# processor.net
KiCad netlist of a schematic drawn in Altium Designer
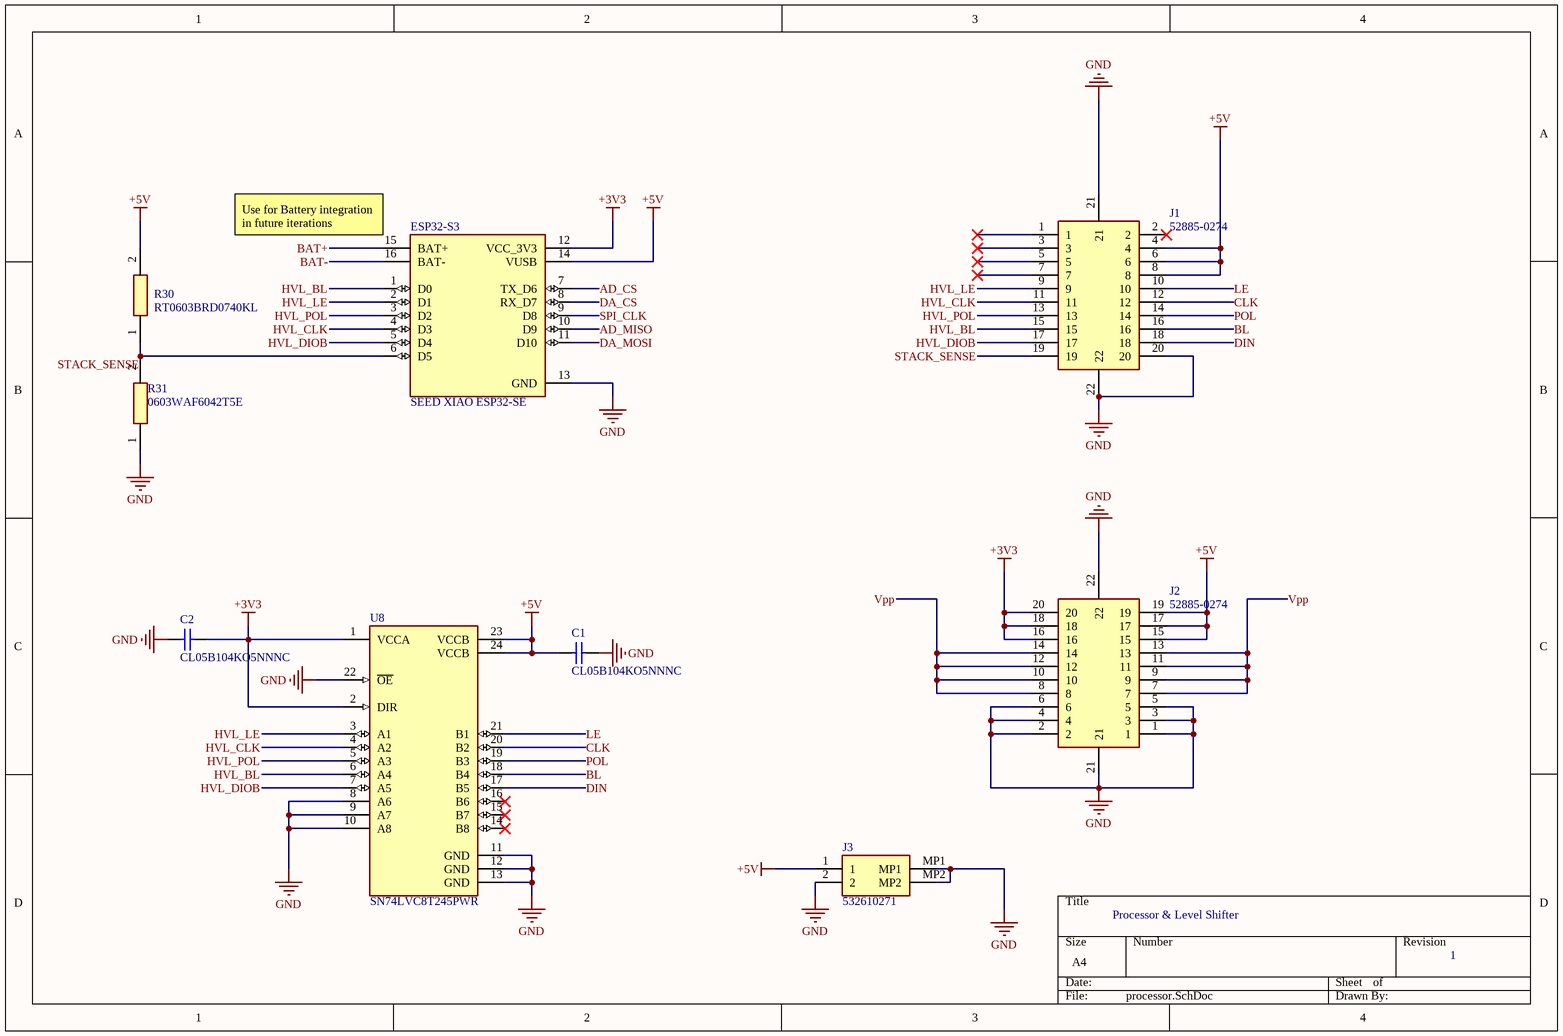
[diagram p0: processor.SchDoc]

(export (version "E")
  (design (tool "Eeschema 10.0.6"))
  (components
    (comp (ref "C1")
      (value "CL05B104KO5NNNC")
      (footprint "CAPC1050X55X23ML05T13")
      (description "Chip Capacitor, 100 nF, +/- 10%, 16 V, -55 to 125 degC, 0402 (1005 Metric), RoHS, Tape and Reel")
      (fields (field (name "MANUFACTURER") "Samsung Electro-Mechanics"))
      (libsource (lib "Altium Content Vault") (part "CAP-NP-2"))
    )
    (comp (ref "C2")
      (value "CL05B104KO5NNNC")
      (footprint "CAPC1050X55X23ML05T13")
      (description "Chip Capacitor, 100 nF, +/- 10%, 16 V, -55 to 125 degC, 0402 (1005 Metric), RoHS, Tape and Reel")
      (fields (field (name "MANUFACTURER") "Samsung Electro-Mechanics"))
      (libsource (lib "Altium Content Vault") (part "CAP-NP-2"))
    )
    (comp (ref "ESP32-S3")
      (value "SEED XIAO ESP32-SE")
      (footprint "PCBComponent_1")
      (libsource (lib "ESP32-S3") (part "Component_1"))
    )
    (comp (ref "J1")
      (value "52885-0274")
      (footprint "528850274")
      (description "Connector")
      (fields (field (name "MOUSER PART NUMBER") "538-52885-0274"))
      (libsource (lib "") (part "52885-0274_1"))
    )
    (comp (ref "J2")
      (value "52885-0274")
      (footprint "528850274")
      (description "Connector")
      (fields (field (name "MOUSER PART NUMBER") "538-52885-0274"))
      (libsource (lib "E_tactile_components") (part "52885-0274"))
    )
    (comp (ref "J3")
      (value "532610271")
      (footprint "SamacSys:532610271")
      (description "C177225")
      (fields
        (field (name "MANUFACTURER_PART_NUMBER") "53261-0271")
        (field (name "MOUSER PART NUMBER") "538-53261-0271")
      )
      (libsource (lib "*") (part "53261-0271"))
    )
    (comp (ref "R30")
      (value "RT0603BRD0740KL")
      (footprint "SamacSys:RESC1608X55N")
      (description "Resistor")
      (fields (field (name "MOUSER PART NUMBER") "603-RT0603BRD0740KL"))
      (libsource (lib "*") (part "RT0603BRD0740KL"))
    )
    (comp (ref "R31")
      (value "0603WAF6042T5E")
      (footprint "SamacSys:RESC1608X55N")
      (description "Resistor")
      (libsource (lib "*") (part "MCT06030C6042FP500"))
    )
    (comp (ref "U8")
      (value "SN74LVC8T245PWR")
      (footprint "FP-PW0024A-MFG")
      (description "IC TRNSLTR BIDIRECTIONAL 24TSSOP")
      (fields
        (field (name "OCTOPART") "https://octopart.com/sn74lvc8t245pwr-texas+instruments-517164")
        (field (name "MANUFACTURER") "Texas Instruments")
      )
      (libsource (lib "Altium Content Vault") (part "51221a7e4c45eff2cf920f7ccaf63e0"))
    )
  )
  (nets
    (net (code "1") (name "+3V3") (class "Default")
      (node (ref "C2") (pin "2") (pinfunction "2_2") (pintype "passive"))
      (node (ref "ESP32-S3") (pin "12") (pinfunction "VCC_3V3_12") (pintype "power_in"))
      (node (ref "J2") (pin "16") (pinfunction "16_16") (pintype "passive"))
      (node (ref "J2") (pin "18") (pinfunction "18_18") (pintype "passive"))
      (node (ref "J2") (pin "20") (pinfunction "20_20") (pintype "passive"))
      (node (ref "U8") (pin "1") (pinfunction "VCCA_1") (pintype "power_in"))
      (node (ref "U8") (pin "2") (pinfunction "DIR_2") (pintype "input"))
    )
    (net (code "2") (name "+5V") (class "Default")
      (node (ref "C1") (pin "1") (pinfunction "1_1") (pintype "passive"))
      (node (ref "ESP32-S3") (pin "14") (pinfunction "VUSB_14") (pintype "power_in"))
      (node (ref "J1") (pin "4") (pinfunction "4_4") (pintype "passive"))
      (node (ref "J1") (pin "6") (pinfunction "6_6") (pintype "passive"))
      (node (ref "J1") (pin "8") (pinfunction "8_8") (pintype "passive"))
      (node (ref "J2") (pin "15") (pinfunction "15_15") (pintype "passive"))
      (node (ref "J2") (pin "17") (pinfunction "17_17") (pintype "passive"))
      (node (ref "J2") (pin "19") (pinfunction "19_19") (pintype "passive"))
      (node (ref "J3") (pin "1") (pinfunction "1_1") (pintype "passive"))
      (node (ref "R30") (pin "2") (pinfunction "2_2") (pintype "passive"))
      (node (ref "U8") (pin "23") (pinfunction "VCCB_23") (pintype "power_in"))
      (node (ref "U8") (pin "24") (pinfunction "VCCB_24") (pintype "power_in"))
    )
    (net (code "3") (name "/AD_CS") (class "Default")
      (node (ref "ESP32-S3") (pin "7") (pinfunction "TX_D6_7") (pintype "bidirectional"))
    )
    (net (code "4") (name "/AD_MISO") (class "Default")
      (node (ref "ESP32-S3") (pin "10") (pinfunction "D9_10") (pintype "bidirectional"))
    )
    (net (code "5") (name "/BAT+") (class "Default")
      (node (ref "ESP32-S3") (pin "15") (pinfunction "BAT+_15") (pintype "passive"))
    )
    (net (code "6") (name "/BAT-") (class "Default")
      (node (ref "ESP32-S3") (pin "16") (pinfunction "BAT-_16") (pintype "passive"))
    )
    (net (code "7") (name "/BL") (class "Default")
      (node (ref "J1") (pin "16") (pinfunction "16_16") (pintype "passive"))
      (node (ref "U8") (pin "18") (pinfunction "B4_18") (pintype "bidirectional"))
    )
    (net (code "8") (name "/CLK") (class "Default")
      (node (ref "J1") (pin "12") (pinfunction "12_12") (pintype "passive"))
      (node (ref "U8") (pin "20") (pinfunction "B2_20") (pintype "bidirectional"))
    )
    (net (code "9") (name "/DA_CS") (class "Default")
      (node (ref "ESP32-S3") (pin "8") (pinfunction "RX_D7_8") (pintype "bidirectional"))
    )
    (net (code "10") (name "/DA_MOSI") (class "Default")
      (node (ref "ESP32-S3") (pin "11") (pinfunction "D10_11") (pintype "bidirectional"))
    )
    (net (code "11") (name "/DIN") (class "Default")
      (node (ref "J1") (pin "18") (pinfunction "18_18") (pintype "passive"))
      (node (ref "U8") (pin "17") (pinfunction "B5_17") (pintype "bidirectional"))
    )
    (net (code "12") (name "/HVL_BL") (class "Default")
      (node (ref "ESP32-S3") (pin "1") (pinfunction "D0_1") (pintype "bidirectional"))
      (node (ref "J1") (pin "15") (pinfunction "15_15") (pintype "passive"))
      (node (ref "U8") (pin "6") (pinfunction "A4_6") (pintype "bidirectional"))
    )
    (net (code "13") (name "/HVL_CLK") (class "Default")
      (node (ref "ESP32-S3") (pin "4") (pinfunction "D3_4") (pintype "bidirectional"))
      (node (ref "J1") (pin "11") (pinfunction "11_11") (pintype "passive"))
      (node (ref "U8") (pin "4") (pinfunction "A2_4") (pintype "bidirectional"))
    )
    (net (code "14") (name "/HVL_DIOB") (class "Default")
      (node (ref "ESP32-S3") (pin "5") (pinfunction "D4_5") (pintype "bidirectional"))
      (node (ref "J1") (pin "17") (pinfunction "17_17") (pintype "passive"))
      (node (ref "U8") (pin "7") (pinfunction "A5_7") (pintype "bidirectional"))
    )
    (net (code "15") (name "/HVL_LE") (class "Default")
      (node (ref "ESP32-S3") (pin "2") (pinfunction "D1_2") (pintype "bidirectional"))
      (node (ref "J1") (pin "9") (pinfunction "9_9") (pintype "passive"))
      (node (ref "U8") (pin "3") (pinfunction "A1_3") (pintype "bidirectional"))
    )
    (net (code "16") (name "/HVL_POL") (class "Default")
      (node (ref "ESP32-S3") (pin "3") (pinfunction "D2_3") (pintype "bidirectional"))
      (node (ref "J1") (pin "13") (pinfunction "13_13") (pintype "passive"))
      (node (ref "U8") (pin "5") (pinfunction "A3_5") (pintype "bidirectional"))
    )
    (net (code "17") (name "/LE") (class "Default")
      (node (ref "J1") (pin "10") (pinfunction "10_10") (pintype "passive"))
      (node (ref "U8") (pin "21") (pinfunction "B1_21") (pintype "bidirectional"))
    )
    (net (code "18") (name "/POL") (class "Default")
      (node (ref "J1") (pin "14") (pinfunction "14_14") (pintype "passive"))
      (node (ref "U8") (pin "19") (pinfunction "B3_19") (pintype "bidirectional"))
    )
    (net (code "19") (name "/SPI_CLK") (class "Default")
      (node (ref "ESP32-S3") (pin "9") (pinfunction "D8_9") (pintype "bidirectional"))
    )
    (net (code "20") (name "/STACK_SENSE") (class "Default")
      (node (ref "ESP32-S3") (pin "6") (pinfunction "D5_6") (pintype "bidirectional"))
      (node (ref "J1") (pin "19") (pinfunction "19_19") (pintype "passive"))
      (node (ref "R30") (pin "1") (pinfunction "1_1") (pintype "passive"))
      (node (ref "R31") (pin "2") (pinfunction "2_2") (pintype "passive"))
    )
    (net (code "21") (name "/Vpp") (class "Default")
      (node (ref "J2") (pin "10") (pinfunction "10_10") (pintype "passive"))
      (node (ref "J2") (pin "11") (pinfunction "11_11") (pintype "passive"))
      (node (ref "J2") (pin "12") (pinfunction "12_12") (pintype "passive"))
      (node (ref "J2") (pin "13") (pinfunction "13_13") (pintype "passive"))
      (node (ref "J2") (pin "14") (pinfunction "14_14") (pintype "passive"))
      (node (ref "J2") (pin "7") (pinfunction "7_7") (pintype "passive"))
      (node (ref "J2") (pin "8") (pinfunction "8_8") (pintype "passive"))
      (node (ref "J2") (pin "9") (pinfunction "9_9") (pintype "passive"))
    )
    (net (code "22") (name "GND") (class "Default")
      (node (ref "C1") (pin "2") (pinfunction "2_2") (pintype "passive"))
      (node (ref "C2") (pin "1") (pinfunction "1_1") (pintype "passive"))
      (node (ref "ESP32-S3") (pin "13") (pinfunction "GND_13") (pintype "power_in"))
      (node (ref "J1") (pin "20") (pinfunction "20_20") (pintype "passive"))
      (node (ref "J1") (pin "21") (pinfunction "21_21") (pintype "passive"))
      (node (ref "J1") (pin "22") (pinfunction "22_22") (pintype "passive"))
      (node (ref "J2") (pin "1") (pinfunction "1_1") (pintype "passive"))
      (node (ref "J2") (pin "2") (pinfunction "2_2") (pintype "passive"))
      (node (ref "J2") (pin "21") (pinfunction "21_21") (pintype "passive"))
      (node (ref "J2") (pin "22") (pinfunction "22_22") (pintype "passive"))
      (node (ref "J2") (pin "3") (pinfunction "3_3") (pintype "passive"))
      (node (ref "J2") (pin "4") (pinfunction "4_4") (pintype "passive"))
      (node (ref "J2") (pin "5") (pinfunction "5_5") (pintype "passive"))
      (node (ref "J2") (pin "6") (pinfunction "6_6") (pintype "passive"))
      (node (ref "J3") (pin "2") (pinfunction "2_2") (pintype "passive"))
      (node (ref "J3") (pin "MP1") (pinfunction "MP1_MP1") (pintype "passive"))
      (node (ref "J3") (pin "MP2") (pinfunction "MP2_MP2") (pintype "passive"))
      (node (ref "R31") (pin "1") (pinfunction "1_1") (pintype "passive"))
      (node (ref "U8") (pin "10") (pinfunction "A8_10") (pintype "passive"))
      (node (ref "U8") (pin "11") (pinfunction "GND_11") (pintype "power_in"))
      (node (ref "U8") (pin "12") (pinfunction "GND_12") (pintype "power_in"))
      (node (ref "U8") (pin "13") (pinfunction "GND_13") (pintype "power_in"))
      (node (ref "U8") (pin "22") (pinfunction "~{OE}_22") (pintype "input"))
      (node (ref "U8") (pin "8") (pinfunction "A6_8") (pintype "passive"))
      (node (ref "U8") (pin "9") (pinfunction "A7_9") (pintype "passive"))
    )
    (net (code "23") (name "unconnected-(J1-Pad1)") (class "Default")
      (node (ref "J1") (pin "1") (pinfunction "1_1") (pintype "passive+no_connect"))
    )
    (net (code "24") (name "unconnected-(J1-Pad2)") (class "Default")
      (node (ref "J1") (pin "2") (pinfunction "2_2") (pintype "passive+no_connect"))
    )
    (net (code "25") (name "unconnected-(J1-Pad3)") (class "Default")
      (node (ref "J1") (pin "3") (pinfunction "3_3") (pintype "passive+no_connect"))
    )
    (net (code "26") (name "unconnected-(J1-Pad5)") (class "Default")
      (node (ref "J1") (pin "5") (pinfunction "5_5") (pintype "passive+no_connect"))
    )
    (net (code "27") (name "unconnected-(J1-Pad7)") (class "Default")
      (node (ref "J1") (pin "7") (pinfunction "7_7") (pintype "passive+no_connect"))
    )
    (net (code "28") (name "unconnected-(U8-B6-Pad16)") (class "Default")
      (node (ref "U8") (pin "16") (pinfunction "B6_16") (pintype "bidirectional+no_connect"))
    )
    (net (code "29") (name "unconnected-(U8-B7-Pad15)") (class "Default")
      (node (ref "U8") (pin "15") (pinfunction "B7_15") (pintype "bidirectional+no_connect"))
    )
    (net (code "30") (name "unconnected-(U8-B8-Pad14)") (class "Default")
      (node (ref "U8") (pin "14") (pinfunction "B8_14") (pintype "bidirectional+no_connect"))
    )
  )
)
